# firecam.net
KiCad netlist of a schematic drawn in EAGLE
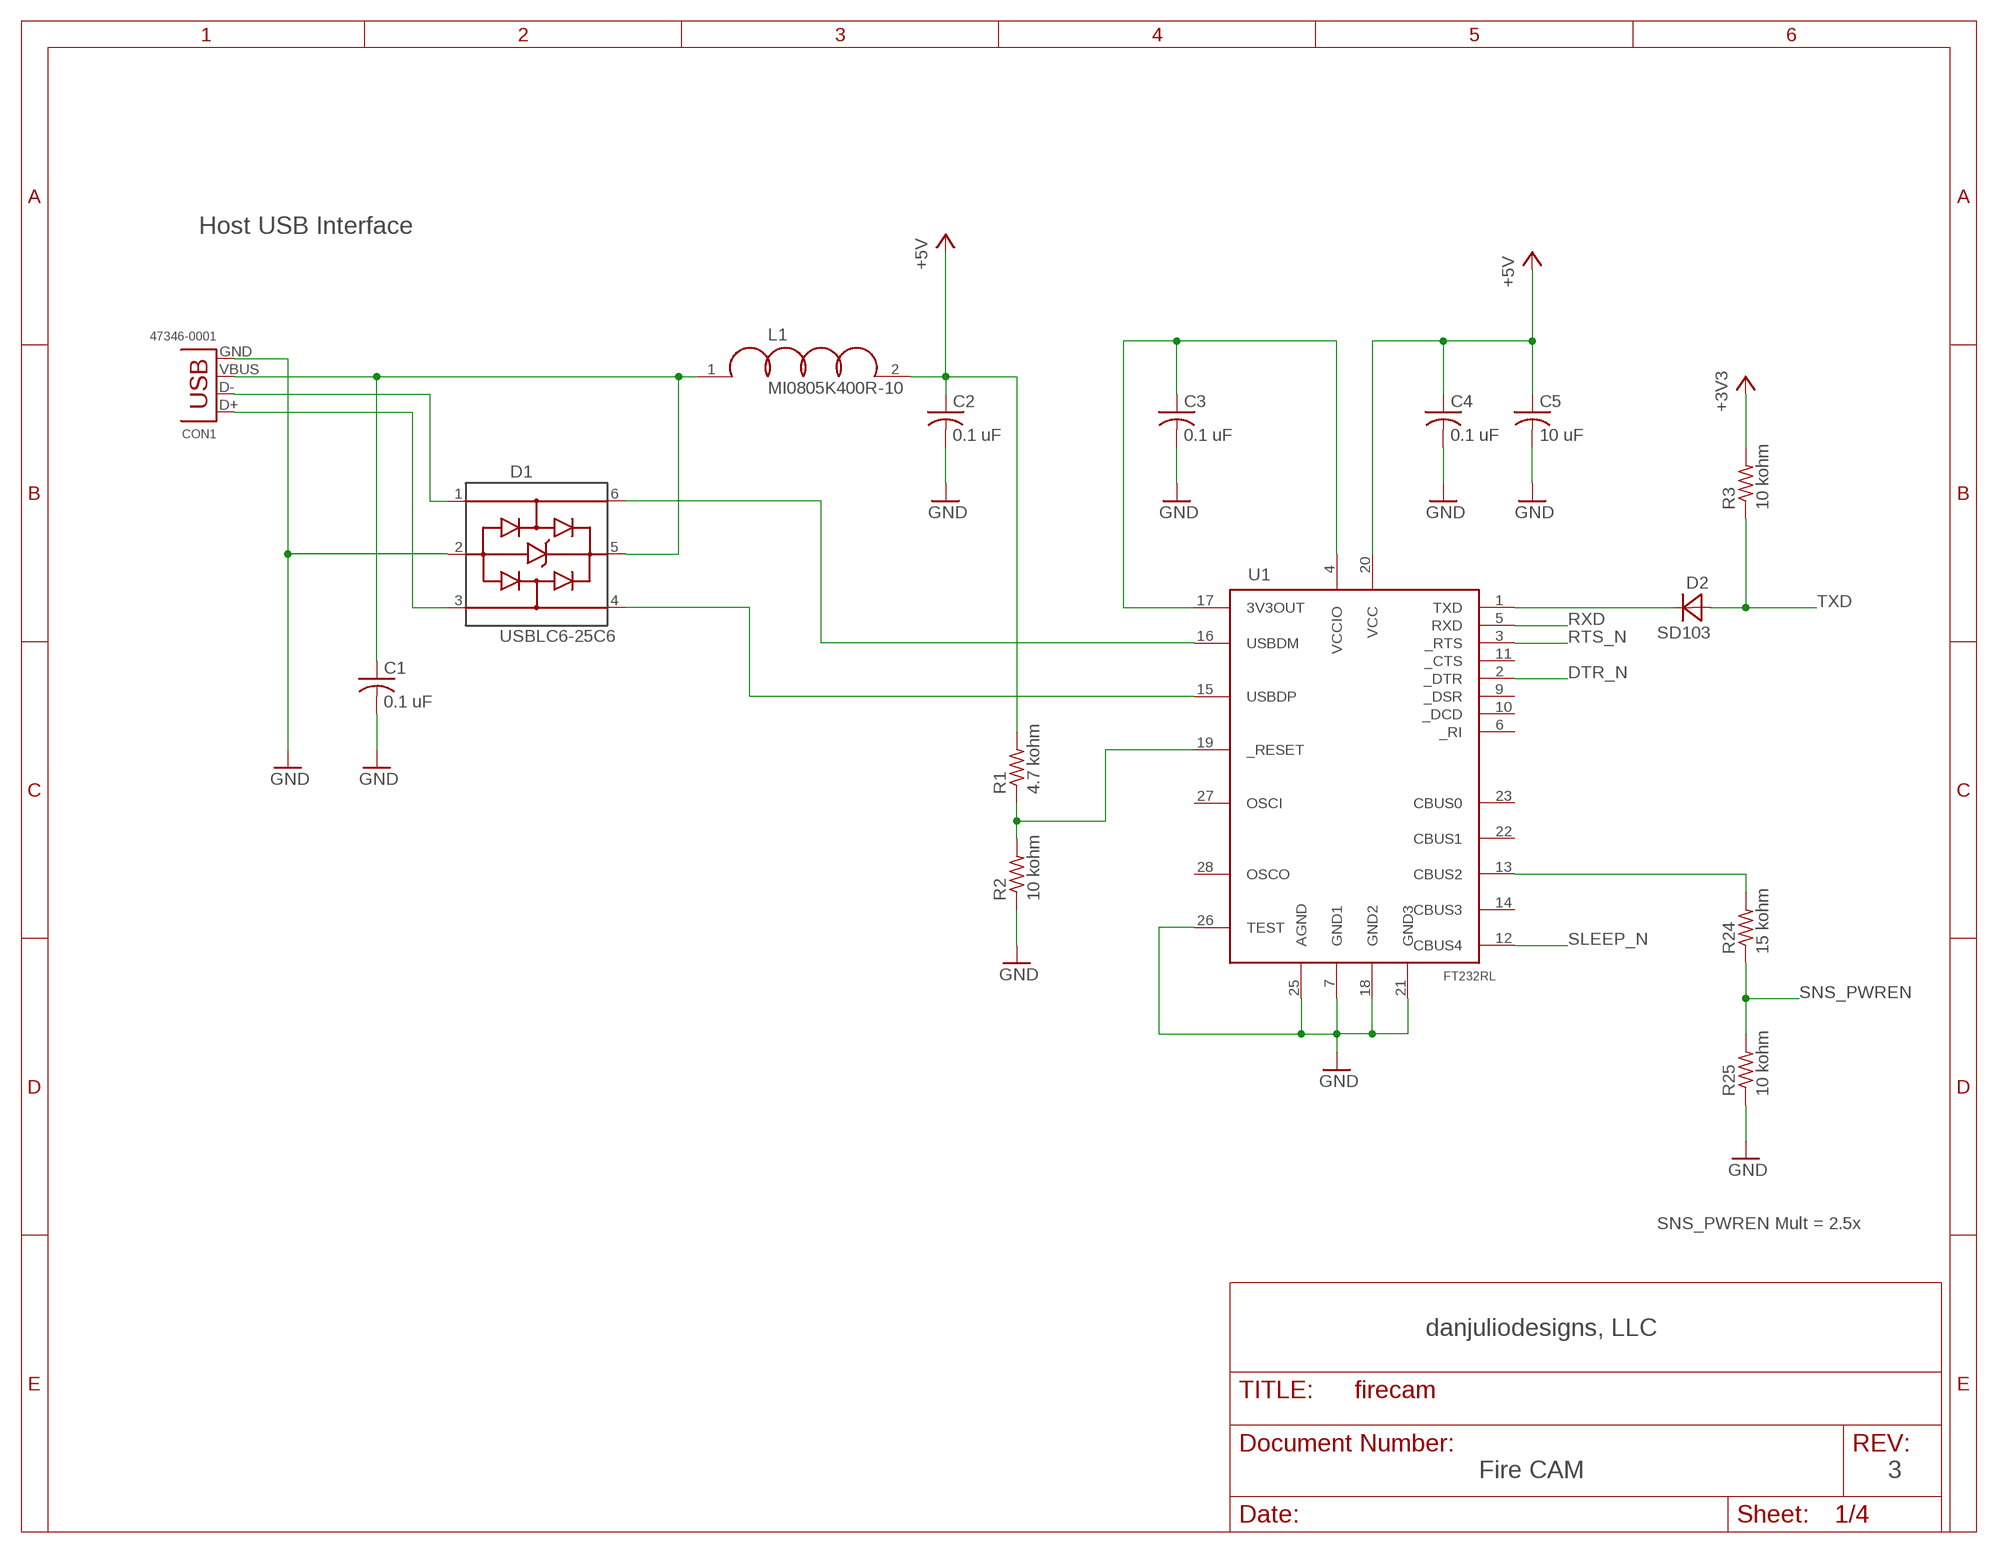
[diagram p0: schematic, sheet 1]
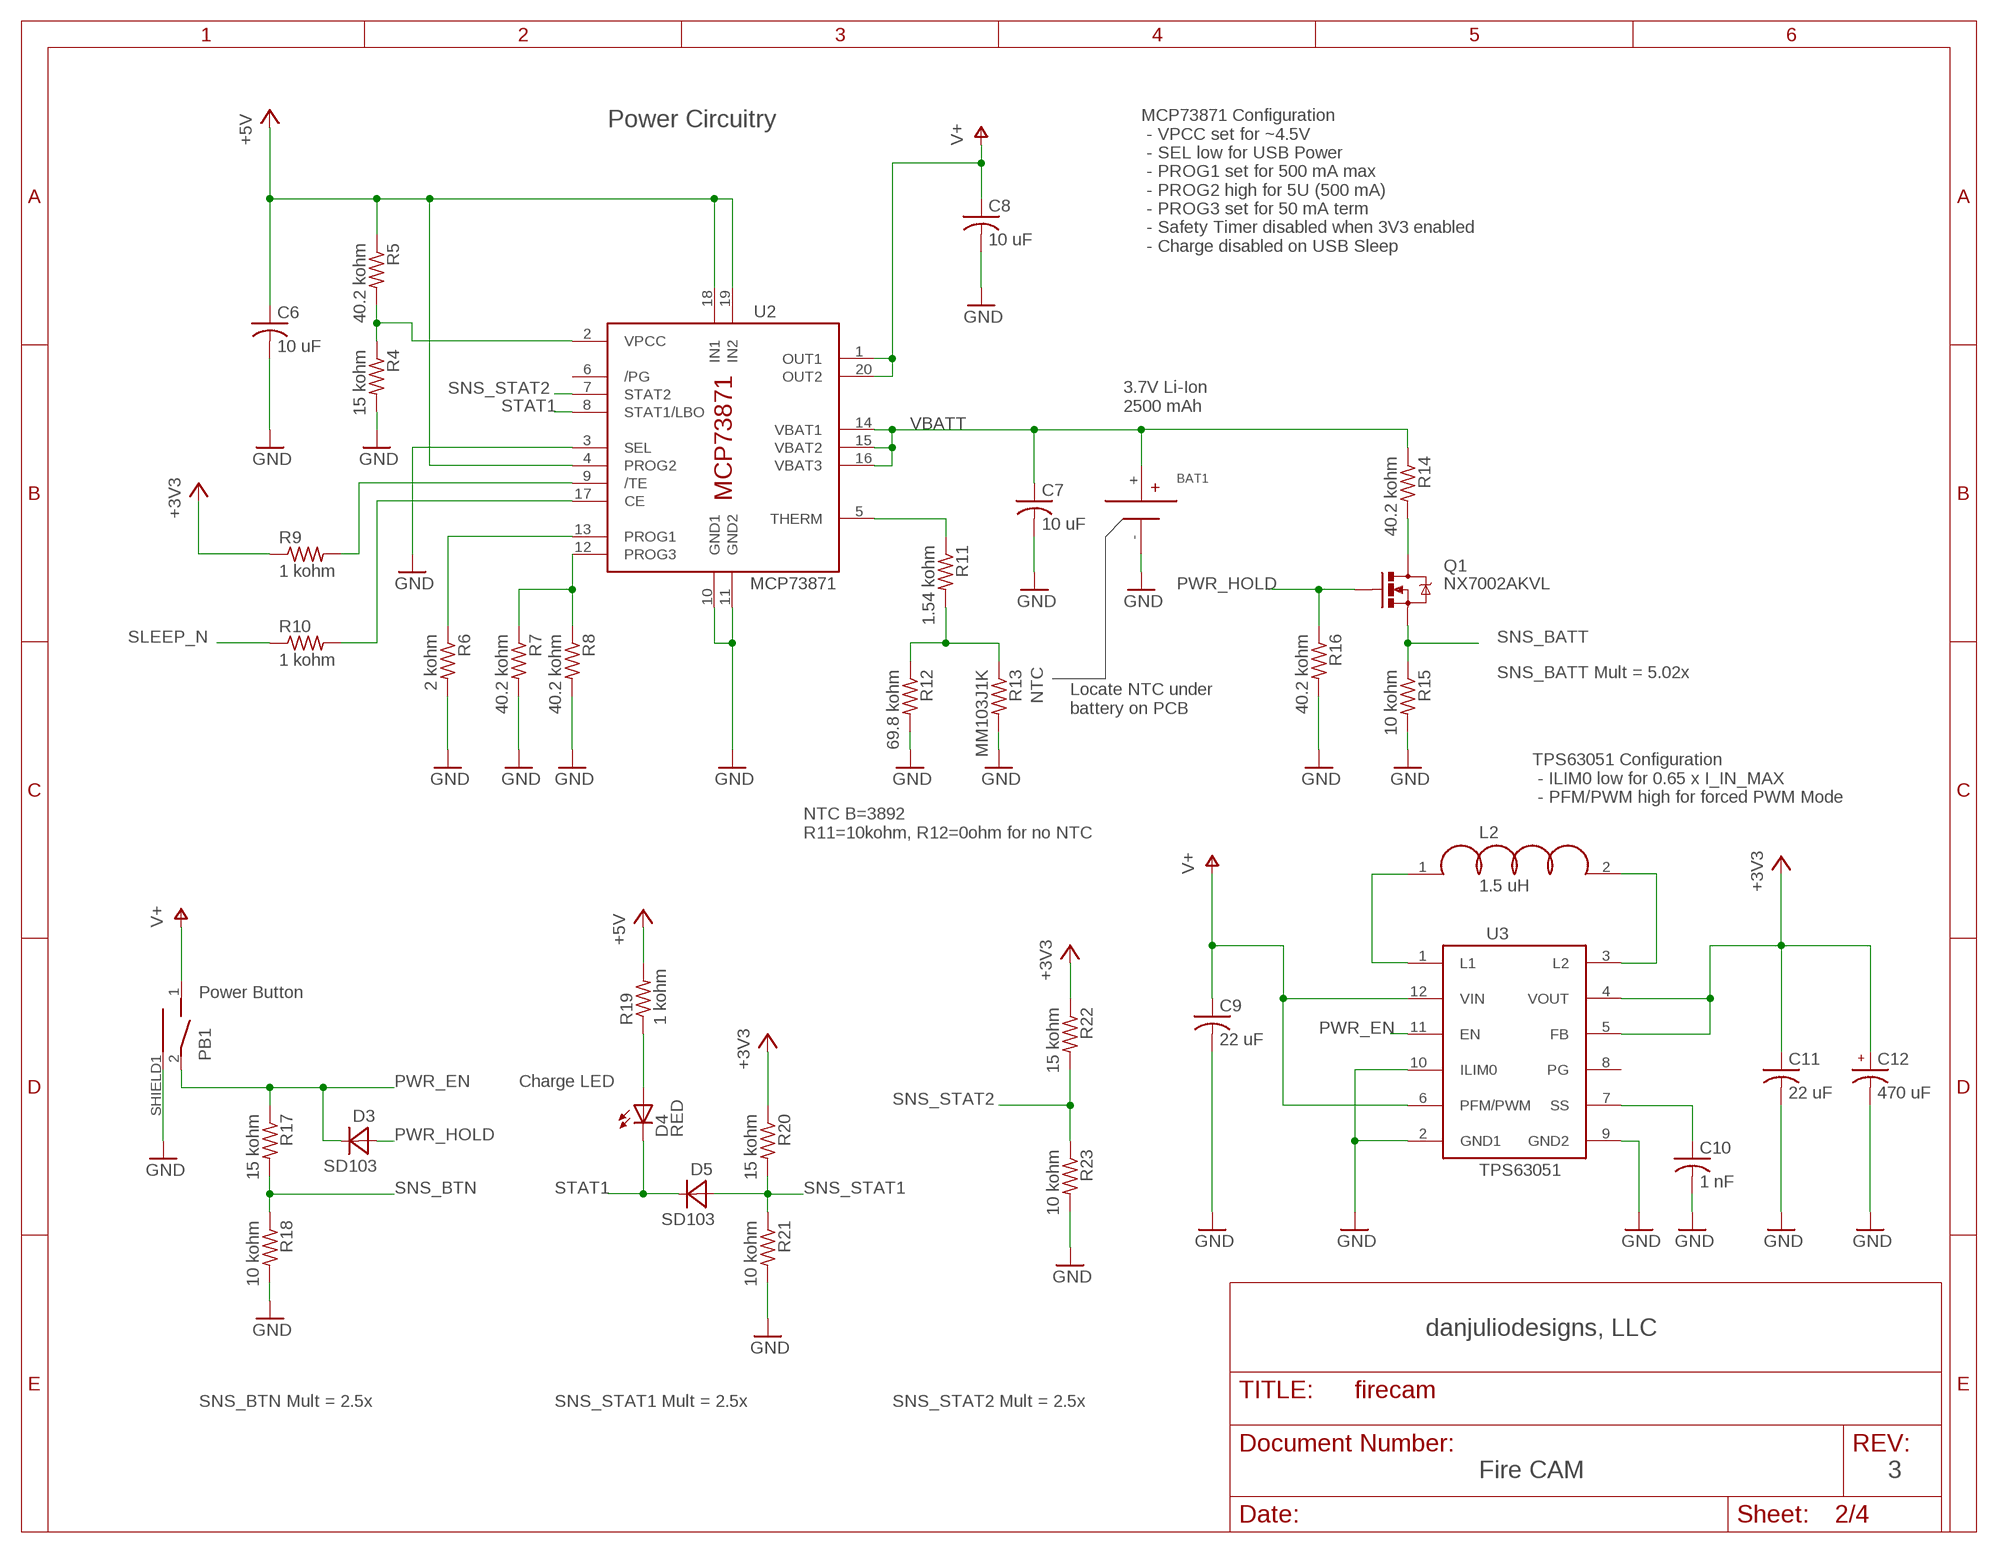
[diagram p1: schematic, sheet 2]
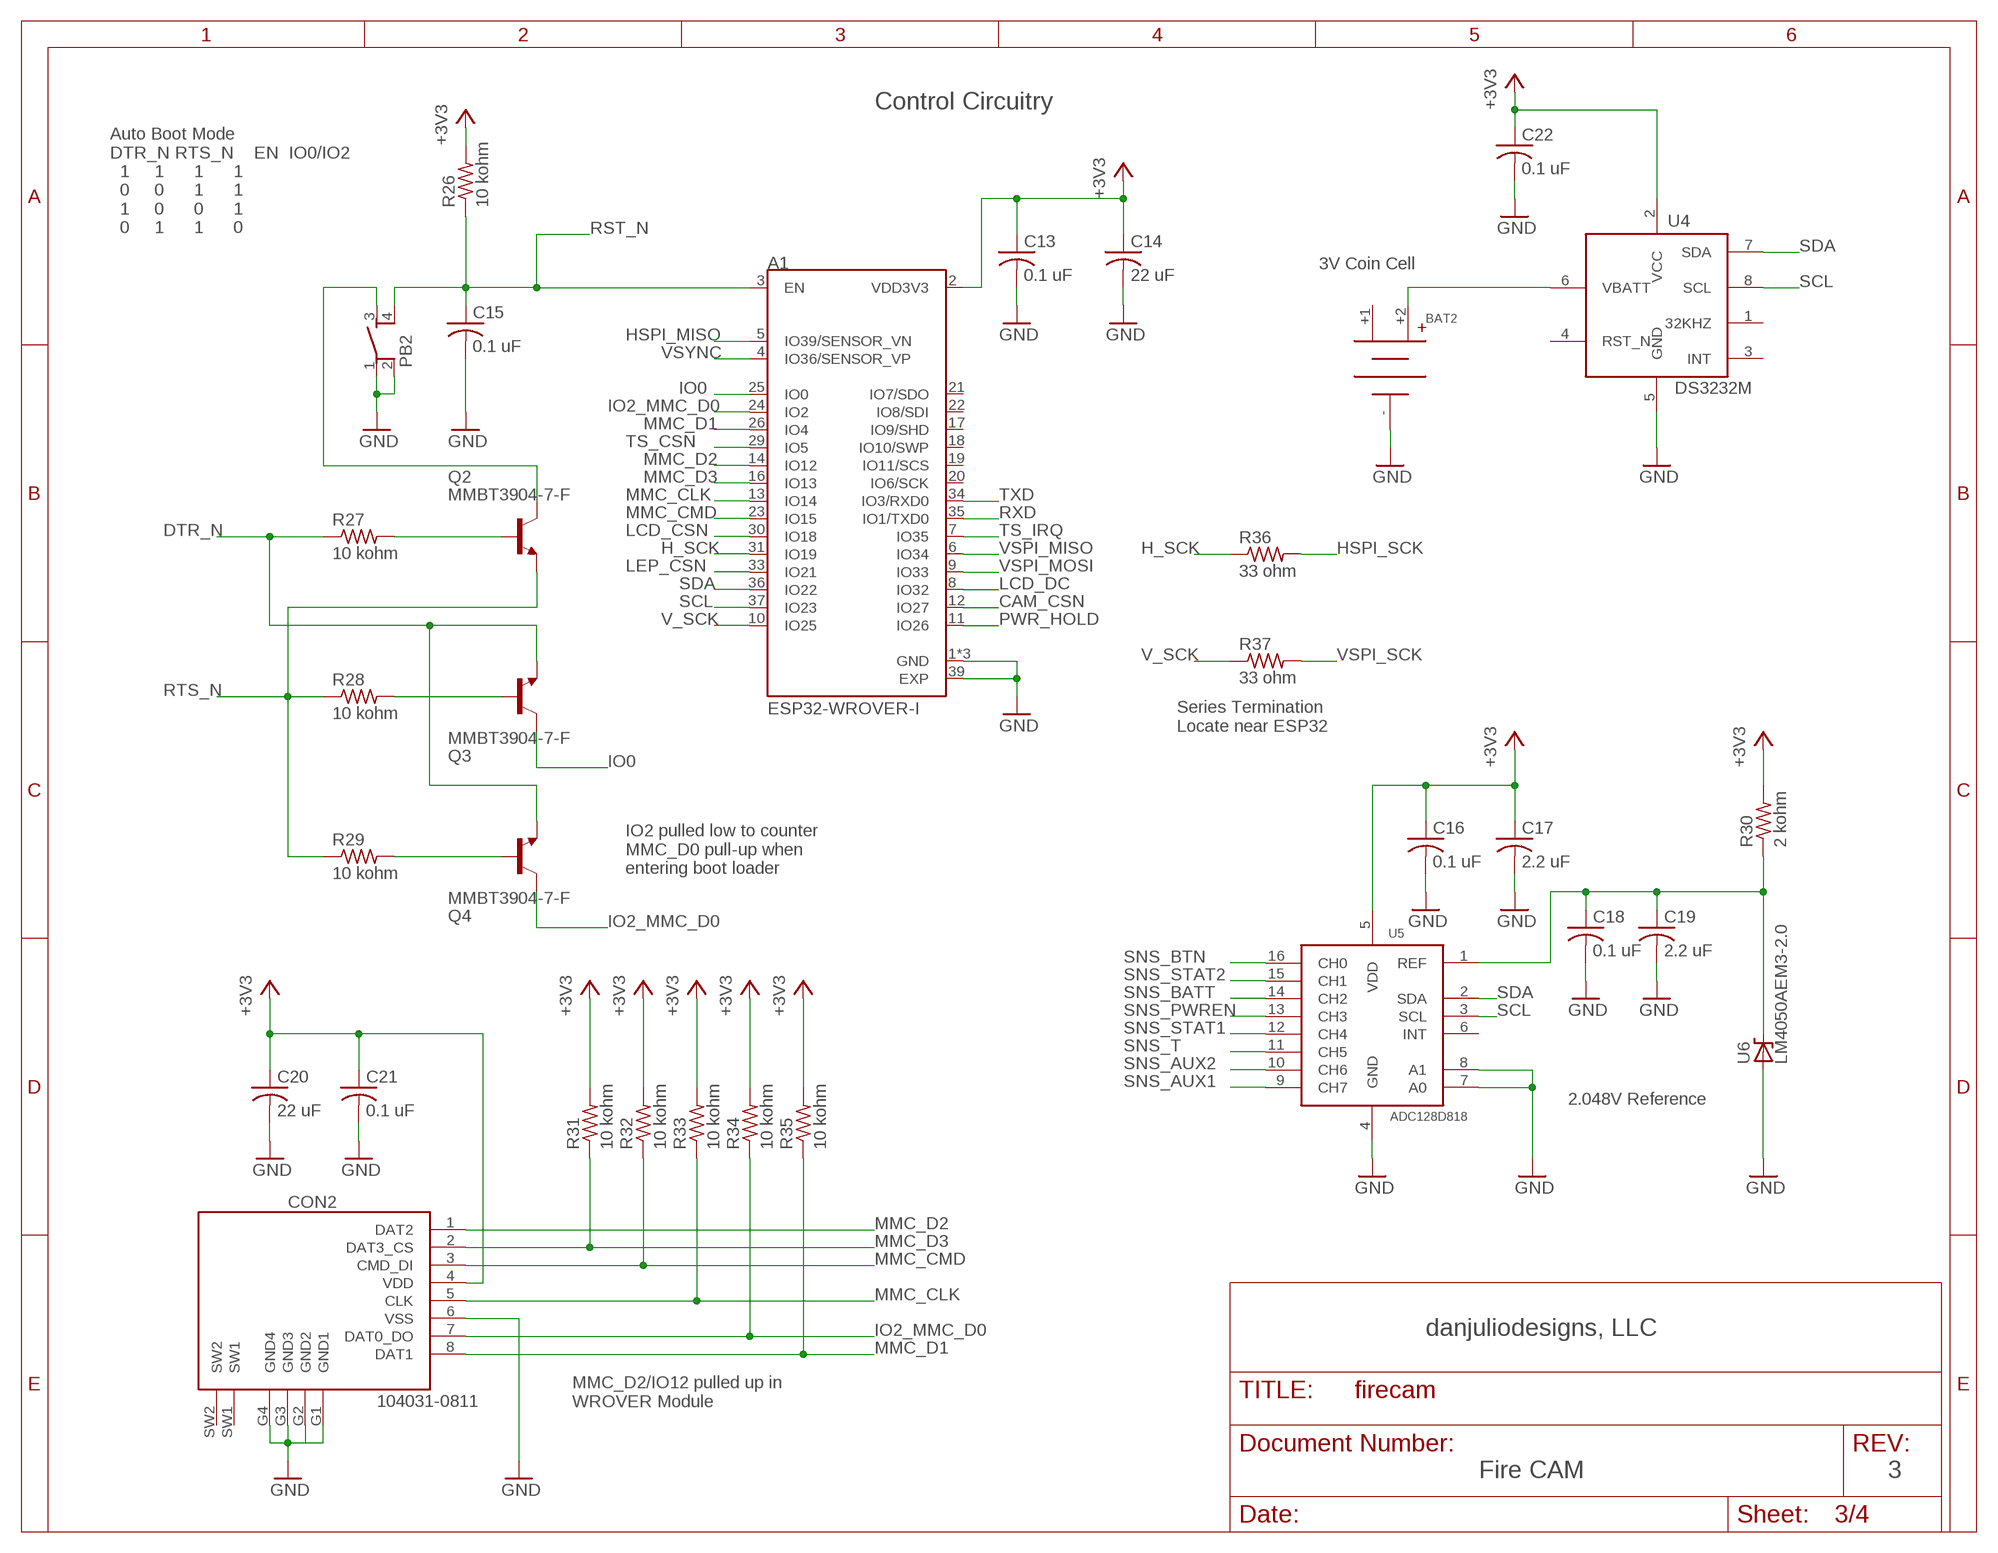
[diagram p2: schematic, sheet 3]
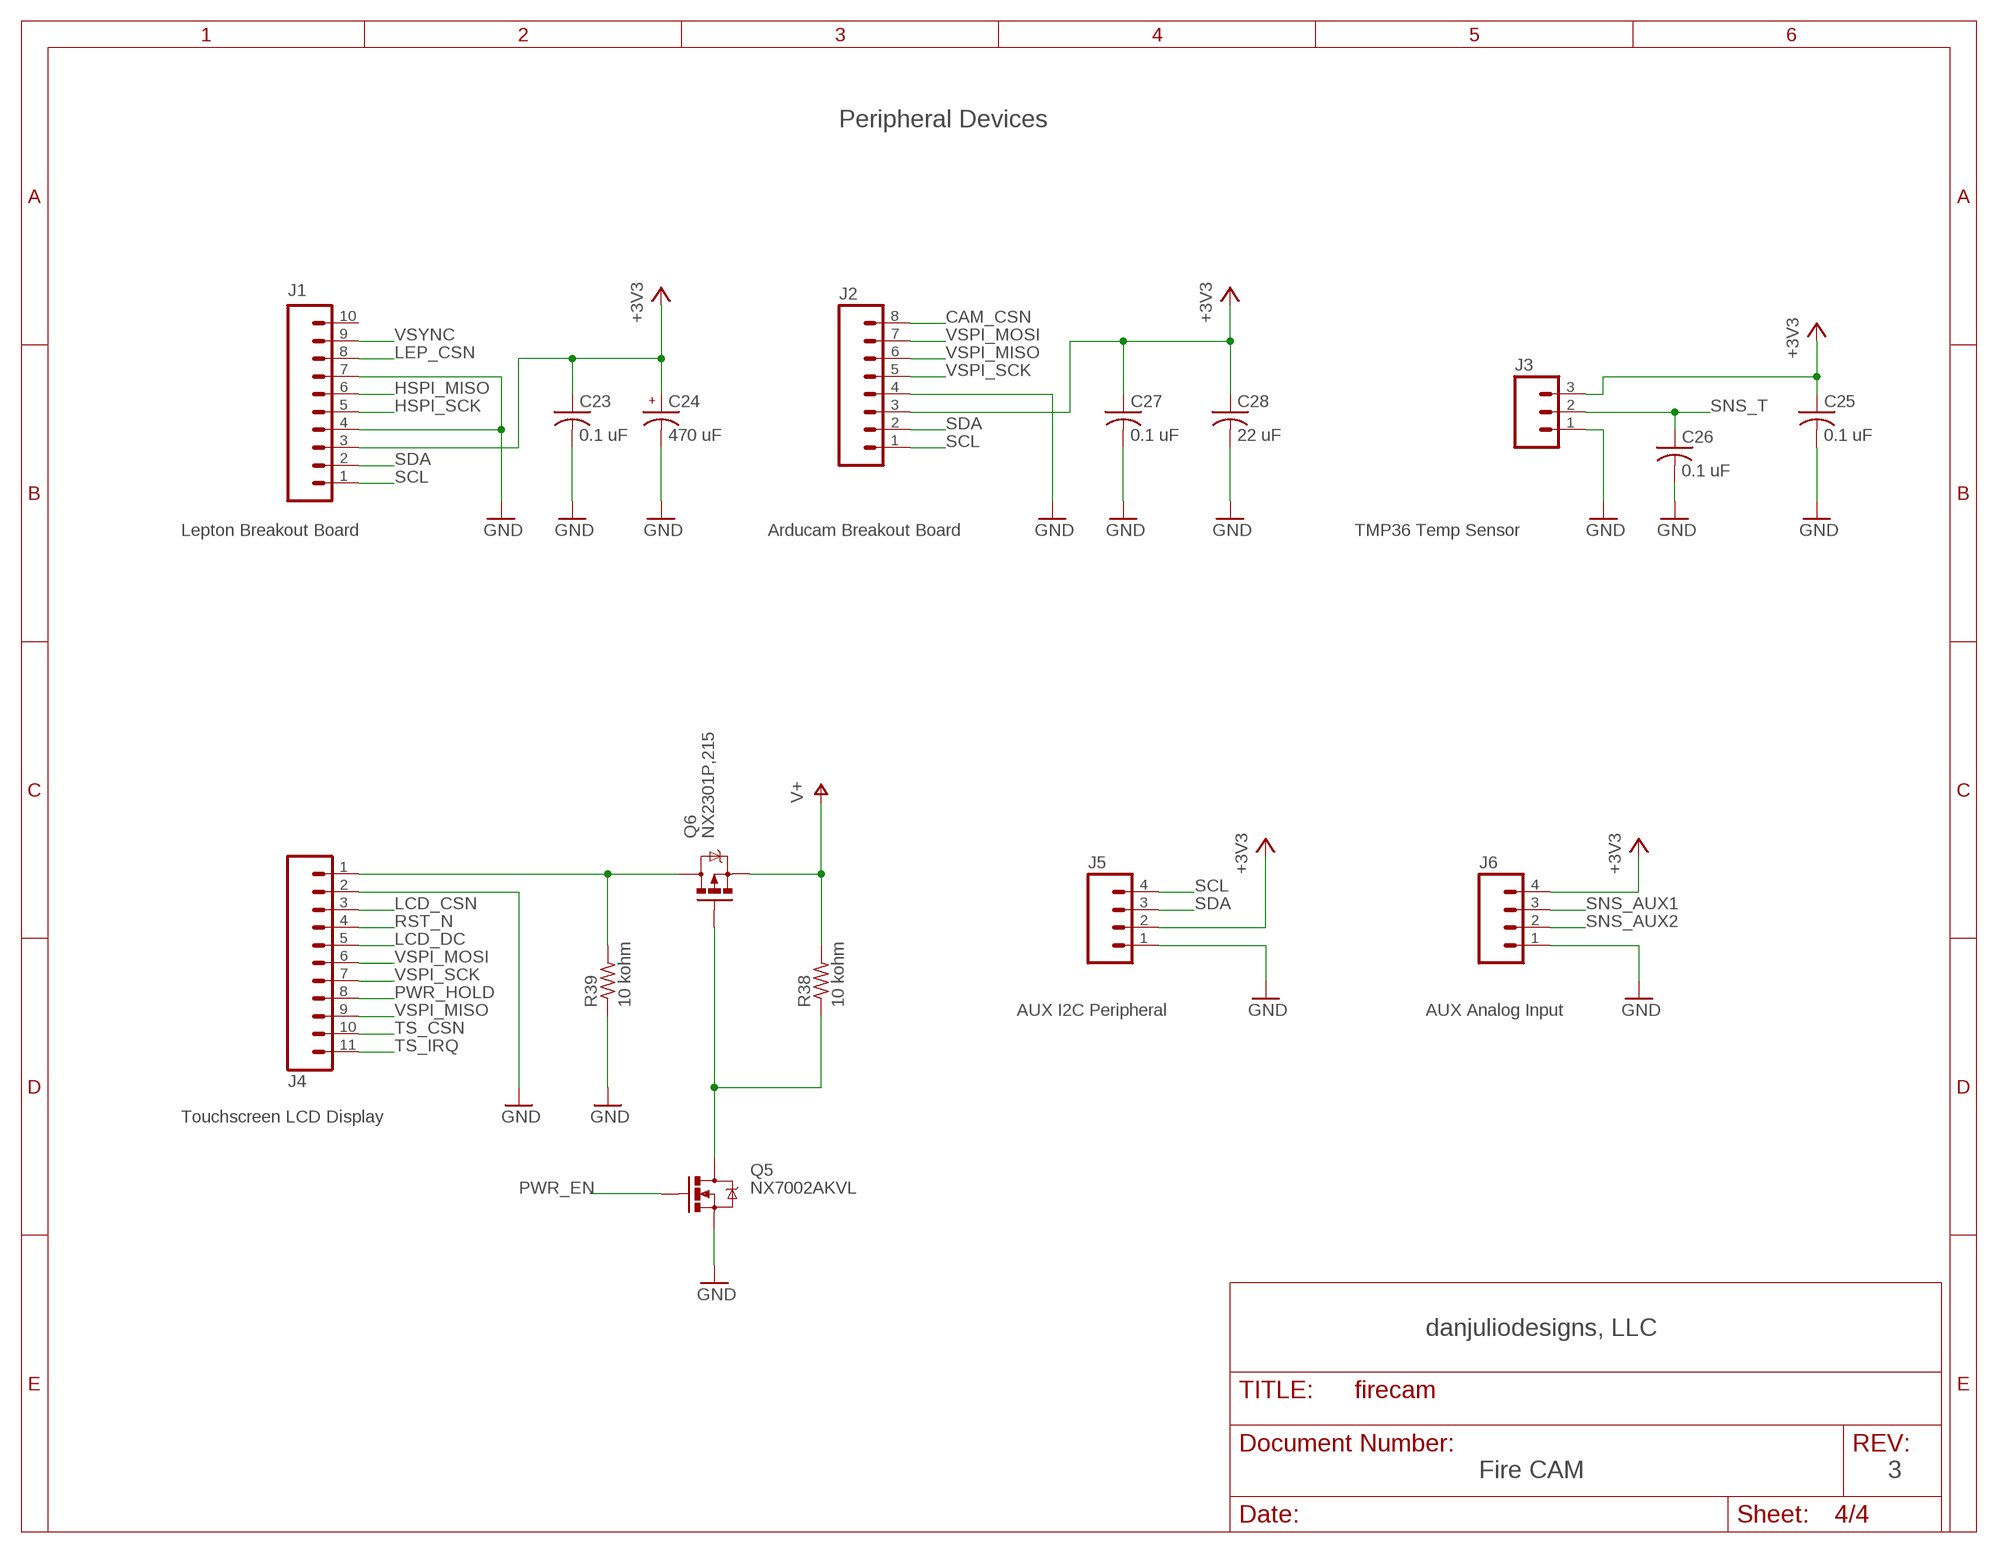
[diagram p3: schematic, sheet 4]

(export (version "E")
  (design (tool "Eeschema 10.0.6"))
  (components
    (comp (ref "C23")
      (value "0.1 uF")
      (footprint "eagle-import:C0603")
      (libsource (lib "eagle-import") (part "C-USSMT0603"))
    )
    (comp (ref "C24")
      (value "470 uF")
      (footprint "eagle-import:ECAP-0606")
      (libsource (lib "eagle-import") (part "CPOL-USSMT06X06"))
    )
    (comp (ref "C25")
      (value "0.1 uF")
      (footprint "eagle-import:C0603")
      (libsource (lib "eagle-import") (part "C-USSMT0603"))
    )
    (comp (ref "C26")
      (value "0.1 uF")
      (footprint "eagle-import:C0603")
      (libsource (lib "eagle-import") (part "C-USSMT0603"))
    )
    (comp (ref "C27")
      (value "0.1 uF")
      (footprint "eagle-import:C0603")
      (libsource (lib "eagle-import") (part "C-USSMT0603"))
    )
    (comp (ref "C28")
      (value "22 uF")
      (footprint "eagle-import:C0603")
      (libsource (lib "eagle-import") (part "C-USSMT0603"))
    )
    (comp (ref "J1")
      (value "M10SILK_FEMALE_PTH")
      (footprint "eagle-import:1X10")
      (libsource (lib "eagle-import") (part "M10SILK_FEMALE_PTH"))
    )
    (comp (ref "J2")
      (value "M08SILK_FEMALE_PTH")
      (footprint "eagle-import:1X08")
      (libsource (lib "eagle-import") (part "M08SILK_FEMALE_PTH"))
    )
    (comp (ref "J3")
      (value "M03PTH")
      (footprint "eagle-import:1X03")
      (libsource (lib "eagle-import") (part "M03PTH"))
    )
    (comp (ref "J4")
      (value "M11PTH")
      (footprint "eagle-import:1X11")
      (libsource (lib "eagle-import") (part "M11PTH"))
    )
    (comp (ref "J5")
      (value "M04PTH")
      (footprint "eagle-import:1X04")
      (libsource (lib "eagle-import") (part "M04PTH"))
    )
    (comp (ref "J6")
      (value "M04PTH")
      (footprint "eagle-import:1X04")
      (libsource (lib "eagle-import") (part "M04PTH"))
    )
    (comp (ref "Q5")
      (value "NX7002AKVL")
      (footprint "eagle-import:SOT23-3")
      (libsource (lib "eagle-import") (part "MOSFET-NCHANNELSOT23"))
    )
    (comp (ref "Q6")
      (value "NX2301P,215")
      (footprint "eagle-import:SOT23-3")
      (libsource (lib "eagle-import") (part "MOSFET-PCHANNEL"))
    )
    (comp (ref "R38")
      (value "10 kohm")
      (footprint "eagle-import:R0603")
      (libsource (lib "eagle-import") (part "R-USSMT0603"))
    )
    (comp (ref "R39")
      (value "10 kohm")
      (footprint "eagle-import:R0603")
      (libsource (lib "eagle-import") (part "R-USSMT0603"))
    )
    (comp (ref "BAT1")
      (value "18650_BATTERYTH")
      (footprint "eagle-import:KEYSTONE_1043")
      (libsource (lib "eagle-import") (part "18650_BATTERYTH"))
    )
    (comp (ref "C6")
      (value "10 uF")
      (footprint "eagle-import:C0603")
      (libsource (lib "eagle-import") (part "C-USSMT0603"))
    )
    (comp (ref "C7")
      (value "10 uF")
      (footprint "eagle-import:C0603")
      (libsource (lib "eagle-import") (part "C-USSMT0603"))
    )
    (comp (ref "C8")
      (value "10 uF")
      (footprint "eagle-import:C0603")
      (libsource (lib "eagle-import") (part "C-USSMT0603"))
    )
    (comp (ref "C9")
      (value "22 uF")
      (footprint "eagle-import:C0603")
      (libsource (lib "eagle-import") (part "C-USSMT0603"))
    )
    (comp (ref "C10")
      (value "1 nF")
      (footprint "eagle-import:C0603")
      (libsource (lib "eagle-import") (part "C-USSMT0603"))
    )
    (comp (ref "C11")
      (value "22 uF")
      (footprint "eagle-import:C0603")
      (libsource (lib "eagle-import") (part "C-USSMT0603"))
    )
    (comp (ref "C12")
      (value "470 uF")
      (footprint "eagle-import:ECAP-0606")
      (libsource (lib "eagle-import") (part "CPOL-USSMT06X06"))
    )
    (comp (ref "D3")
      (value "SD103")
      (footprint "eagle-import:SOD123")
      (libsource (lib "eagle-import") (part "DIODESMT_SOD123"))
    )
    (comp (ref "D4")
      (value "RED")
      (footprint "eagle-import:LUMEX_3MM_SMT")
      (libsource (lib "eagle-import") (part "LEDLUMEX_SMT_3MM"))
    )
    (comp (ref "D5")
      (value "SD103")
      (footprint "eagle-import:SOD123")
      (libsource (lib "eagle-import") (part "DIODESMT_SOD123"))
    )
    (comp (ref "L2")
      (value "1.5 uH")
      (footprint "eagle-import:L1008")
      (libsource (lib "eagle-import") (part "INDUCTORSMT1008"))
    )
    (comp (ref "PB1")
      (value "PB_SMT_SIDEPTS645")
      (footprint "eagle-import:PTS645_SIDE_TH")
      (libsource (lib "eagle-import") (part "PB_SMT_SIDEPTS645"))
    )
    (comp (ref "Q1")
      (value "NX7002AKVL")
      (footprint "eagle-import:SOT23-3")
      (libsource (lib "eagle-import") (part "MOSFET-NCHANNELSOT23"))
    )
    (comp (ref "R4")
      (value "15 kohm")
      (footprint "eagle-import:R0603")
      (libsource (lib "eagle-import") (part "R-USSMT0603"))
    )
    (comp (ref "R5")
      (value "40.2 kohm")
      (footprint "eagle-import:R0603")
      (libsource (lib "eagle-import") (part "R-USSMT0603"))
    )
    (comp (ref "R6")
      (value "2 kohm")
      (footprint "eagle-import:R0603")
      (libsource (lib "eagle-import") (part "R-USSMT0603"))
    )
    (comp (ref "R7")
      (value "40.2 kohm")
      (footprint "eagle-import:R0603")
      (libsource (lib "eagle-import") (part "R-USSMT0603"))
    )
    (comp (ref "R8")
      (value "40.2 kohm")
      (footprint "eagle-import:R0603")
      (libsource (lib "eagle-import") (part "R-USSMT0603"))
    )
    (comp (ref "R9")
      (value "1 kohm")
      (footprint "eagle-import:R0603")
      (libsource (lib "eagle-import") (part "R-USSMT0603"))
    )
    (comp (ref "R10")
      (value "1 kohm")
      (footprint "eagle-import:R0603")
      (libsource (lib "eagle-import") (part "R-USSMT0603"))
    )
    (comp (ref "R11")
      (value "1.54 kohm")
      (footprint "eagle-import:R0603")
      (libsource (lib "eagle-import") (part "R-USSMT0603"))
    )
    (comp (ref "R12")
      (value "69.8 kohm")
      (footprint "eagle-import:R0603")
      (libsource (lib "eagle-import") (part "R-USSMT0603"))
    )
    (comp (ref "R13")
      (value "MM103J1K")
      (footprint "eagle-import:R0603")
      (libsource (lib "eagle-import") (part "R-USSMT0603"))
    )
    (comp (ref "R14")
      (value "40.2 kohm")
      (footprint "eagle-import:R0603")
      (libsource (lib "eagle-import") (part "R-USSMT0603"))
    )
    (comp (ref "R15")
      (value "10 kohm")
      (footprint "eagle-import:R0603")
      (libsource (lib "eagle-import") (part "R-USSMT0603"))
    )
    (comp (ref "R16")
      (value "40.2 kohm")
      (footprint "eagle-import:R0603")
      (libsource (lib "eagle-import") (part "R-USSMT0603"))
    )
    (comp (ref "R17")
      (value "15 kohm")
      (footprint "eagle-import:R0603")
      (libsource (lib "eagle-import") (part "R-USSMT0603"))
    )
    (comp (ref "R18")
      (value "10 kohm")
      (footprint "eagle-import:R0603")
      (libsource (lib "eagle-import") (part "R-USSMT0603"))
    )
    (comp (ref "R19")
      (value "1 kohm")
      (footprint "eagle-import:R0603")
      (libsource (lib "eagle-import") (part "R-USSMT0603"))
    )
    (comp (ref "R20")
      (value "15 kohm")
      (footprint "eagle-import:R0603")
      (libsource (lib "eagle-import") (part "R-USSMT0603"))
    )
    (comp (ref "R21")
      (value "10 kohm")
      (footprint "eagle-import:R0603")
      (libsource (lib "eagle-import") (part "R-USSMT0603"))
    )
    (comp (ref "R22")
      (value "15 kohm")
      (footprint "eagle-import:R0603")
      (libsource (lib "eagle-import") (part "R-USSMT0603"))
    )
    (comp (ref "R23")
      (value "10 kohm")
      (footprint "eagle-import:R0603")
      (libsource (lib "eagle-import") (part "R-USSMT0603"))
    )
    (comp (ref "U2")
      (value "MCP73871")
      (footprint "eagle-import:QFN20")
      (libsource (lib "eagle-import") (part "MCP73871"))
    )
    (comp (ref "U3")
      (value "TPS63051")
      (footprint "eagle-import:HOTROD_QFN12")
      (libsource (lib "eagle-import") (part "TPS63051_QFN"))
    )
    (comp (ref "A1")
      (value "ESP32-WROVER-I")
      (footprint "eagle-import:XCVR_ESP32-WROVER-I")
      (fields (field (name "MF") "Espressif Systems"))
      (libsource (lib "eagle-import") (part "ESP32-WROVER-I"))
    )
    (comp (ref "BAT2")
      (value "COIN_CELL12MM")
      (footprint "eagle-import:KEYSTONE_3001")
      (libsource (lib "eagle-import") (part "COIN_CELL12MM"))
    )
    (comp (ref "C13")
      (value "0.1 uF")
      (footprint "eagle-import:C0603")
      (libsource (lib "eagle-import") (part "C-USSMT0603"))
    )
    (comp (ref "C14")
      (value "22 uF")
      (footprint "eagle-import:C0603")
      (libsource (lib "eagle-import") (part "C-USSMT0603"))
    )
    (comp (ref "C15")
      (value "0.1 uF")
      (footprint "eagle-import:C0603")
      (libsource (lib "eagle-import") (part "C-USSMT0603"))
    )
    (comp (ref "C16")
      (value "0.1 uF")
      (footprint "eagle-import:C0603")
      (libsource (lib "eagle-import") (part "C-USSMT0603"))
    )
    (comp (ref "C17")
      (value "2.2 uF")
      (footprint "eagle-import:C0603")
      (libsource (lib "eagle-import") (part "C-USSMT0603"))
    )
    (comp (ref "C18")
      (value "0.1 uF")
      (footprint "eagle-import:C0603")
      (libsource (lib "eagle-import") (part "C-USSMT0603"))
    )
    (comp (ref "C19")
      (value "2.2 uF")
      (footprint "eagle-import:C0603")
      (libsource (lib "eagle-import") (part "C-USSMT0603"))
    )
    (comp (ref "C20")
      (value "22 uF")
      (footprint "eagle-import:C0603")
      (libsource (lib "eagle-import") (part "C-USSMT0603"))
    )
    (comp (ref "C21")
      (value "0.1 uF")
      (footprint "eagle-import:C0603")
      (libsource (lib "eagle-import") (part "C-USSMT0603"))
    )
    (comp (ref "C22")
      (value "0.1 uF")
      (footprint "eagle-import:C0603")
      (libsource (lib "eagle-import") (part "C-USSMT0603"))
    )
    (comp (ref "CON2")
      (value "104031-0811")
      (footprint "eagle-import:MOLEX_1040310811")
      (libsource (lib "eagle-import") (part "MOLEX_1040310811"))
    )
    (comp (ref "PB2")
      (value "PB_TACT_4SMTR92")
      (footprint "eagle-import:CK_PTS645_SMT")
      (libsource (lib "eagle-import") (part "PB_TACT_4SMTR92"))
    )
    (comp (ref "Q2")
      (value "MMBT3904-7-F")
      (footprint "eagle-import:SOT23-BEC")
      (libsource (lib "eagle-import") (part "-NPN-SOT23-BECBC808"))
    )
    (comp (ref "Q3")
      (value "MMBT3904-7-F")
      (footprint "eagle-import:SOT23-BEC")
      (libsource (lib "eagle-import") (part "-NPN-SOT23-BECBC808"))
    )
    (comp (ref "Q4")
      (value "MMBT3904-7-F")
      (footprint "eagle-import:SOT23-BEC")
      (libsource (lib "eagle-import") (part "-NPN-SOT23-BECBC808"))
    )
    (comp (ref "R26")
      (value "10 kohm")
      (footprint "eagle-import:R0603")
      (libsource (lib "eagle-import") (part "R-USSMT0603"))
    )
    (comp (ref "R27")
      (value "10 kohm")
      (footprint "eagle-import:R0603")
      (libsource (lib "eagle-import") (part "R-USSMT0603"))
    )
    (comp (ref "R28")
      (value "10 kohm")
      (footprint "eagle-import:R0603")
      (libsource (lib "eagle-import") (part "R-USSMT0603"))
    )
    (comp (ref "R29")
      (value "10 kohm")
      (footprint "eagle-import:R0603")
      (libsource (lib "eagle-import") (part "R-USSMT0603"))
    )
    (comp (ref "R30")
      (value "2 kohm")
      (footprint "eagle-import:R0603")
      (libsource (lib "eagle-import") (part "R-USSMT0603"))
    )
    (comp (ref "R31")
      (value "10 kohm")
      (footprint "eagle-import:R0603")
      (libsource (lib "eagle-import") (part "R-USSMT0603"))
    )
    (comp (ref "R32")
      (value "10 kohm")
      (footprint "eagle-import:R0603")
      (libsource (lib "eagle-import") (part "R-USSMT0603"))
    )
    (comp (ref "R33")
      (value "10 kohm")
      (footprint "eagle-import:R0603")
      (libsource (lib "eagle-import") (part "R-USSMT0603"))
    )
    (comp (ref "R34")
      (value "10 kohm")
      (footprint "eagle-import:R0603")
      (libsource (lib "eagle-import") (part "R-USSMT0603"))
    )
    (comp (ref "R35")
      (value "10 kohm")
      (footprint "eagle-import:R0603")
      (libsource (lib "eagle-import") (part "R-USSMT0603"))
    )
    (comp (ref "R36")
      (value "33 ohm")
      (footprint "eagle-import:R0603")
      (libsource (lib "eagle-import") (part "R-USSMT0603"))
    )
    (comp (ref "R37")
      (value "33 ohm")
      (footprint "eagle-import:R0603")
      (libsource (lib "eagle-import") (part "R-USSMT0603"))
    )
    (comp (ref "U4")
      (value "DS3232M")
      (footprint "eagle-import:SO8")
      (libsource (lib "eagle-import") (part "DS3232M"))
    )
    (comp (ref "U5")
      (value "ADC128D818")
      (footprint "eagle-import:SSOP16")
      (libsource (lib "eagle-import") (part "ADC128D818"))
    )
    (comp (ref "U6")
      (value "LM4050AEM3-2.0")
      (footprint "eagle-import:SOT23-3")
      (libsource (lib "eagle-import") (part "VOLTAGE_REFSMT_SOT23"))
    )
    (comp (ref "C1")
      (value "0.1 uF")
      (footprint "eagle-import:C0603")
      (libsource (lib "eagle-import") (part "C-USSMT0603"))
    )
    (comp (ref "C2")
      (value "0.1 uF")
      (footprint "eagle-import:C0603")
      (libsource (lib "eagle-import") (part "C-USSMT0603"))
    )
    (comp (ref "C3")
      (value "0.1 uF")
      (footprint "eagle-import:C0603")
      (libsource (lib "eagle-import") (part "C-USSMT0603"))
    )
    (comp (ref "C4")
      (value "0.1 uF")
      (footprint "eagle-import:C0603")
      (libsource (lib "eagle-import") (part "C-USSMT0603"))
    )
    (comp (ref "C5")
      (value "10 uF")
      (footprint "eagle-import:C0603")
      (libsource (lib "eagle-import") (part "C-USSMT0603"))
    )
    (comp (ref "CON1")
      (value "47346-0001")
      (footprint "eagle-import:USB_MICROB_SMT")
      (libsource (lib "eagle-import") (part "USBMICROB"))
    )
    (comp (ref "D1")
      (value "USBLC6-25C6")
      (footprint "eagle-import:SOT23-6")
      (libsource (lib "eagle-import") (part "USBLC6-2SOT23-6"))
    )
    (comp (ref "D2")
      (value "SD103")
      (footprint "eagle-import:SOD123")
      (libsource (lib "eagle-import") (part "DIODESMT_SOD123"))
    )
    (comp (ref "L1")
      (value "MI0805K400R-10")
      (footprint "eagle-import:L0805")
      (libsource (lib "eagle-import") (part "INDUCTORSMT0805"))
    )
    (comp (ref "R1")
      (value "4.7 kohm")
      (footprint "eagle-import:R0603")
      (libsource (lib "eagle-import") (part "R-USSMT0603"))
    )
    (comp (ref "R2")
      (value "10 kohm")
      (footprint "eagle-import:R0603")
      (libsource (lib "eagle-import") (part "R-USSMT0603"))
    )
    (comp (ref "R3")
      (value "10 kohm")
      (footprint "eagle-import:R0603")
      (libsource (lib "eagle-import") (part "R-USSMT0603"))
    )
    (comp (ref "R24")
      (value "15 kohm")
      (footprint "eagle-import:R0603")
      (libsource (lib "eagle-import") (part "R-USSMT0603"))
    )
    (comp (ref "R25")
      (value "10 kohm")
      (footprint "eagle-import:R0603")
      (libsource (lib "eagle-import") (part "R-USSMT0603"))
    )
    (comp (ref "U1")
      (value "FT232RL")
      (footprint "eagle-import:SSOP28DB")
      (libsource (lib "eagle-import") (part "FT232RLSSOP28"))
    )
  )
  (nets
    (net (code "1") (name "+1") (class "Default")
      (node (ref "BAT2") (pin "+1") (pinfunction "+1_+1") (pintype "power_in"))
    )
    (net (code "2") (name "+3V3") (class "Default")
      (node (ref "A1") (pin "2") (pinfunction "VDD3V3_2") (pintype "power_in"))
      (node (ref "C11") (pin "1") (pinfunction "1_1") (pintype "passive"))
      (node (ref "C12") (pin "+") (pinfunction "1_+") (pintype "passive"))
      (node (ref "C13") (pin "1") (pinfunction "1_1") (pintype "passive"))
      (node (ref "C14") (pin "1") (pinfunction "1_1") (pintype "passive"))
      (node (ref "C16") (pin "1") (pinfunction "1_1") (pintype "passive"))
      (node (ref "C17") (pin "1") (pinfunction "1_1") (pintype "passive"))
      (node (ref "C20") (pin "1") (pinfunction "1_1") (pintype "passive"))
      (node (ref "C21") (pin "1") (pinfunction "1_1") (pintype "passive"))
      (node (ref "C22") (pin "1") (pinfunction "1_1") (pintype "passive"))
      (node (ref "C23") (pin "1") (pinfunction "1_1") (pintype "passive"))
      (node (ref "C24") (pin "+") (pinfunction "1_+") (pintype "passive"))
      (node (ref "C25") (pin "1") (pinfunction "1_1") (pintype "passive"))
      (node (ref "C27") (pin "1") (pinfunction "1_1") (pintype "passive"))
      (node (ref "C28") (pin "1") (pinfunction "1_1") (pintype "passive"))
      (node (ref "CON2") (pin "4") (pinfunction "VDD_4") (pintype "power_in"))
      (node (ref "J1") (pin "3") (pinfunction "3_3") (pintype "passive"))
      (node (ref "J2") (pin "3") (pinfunction "3_3") (pintype "passive"))
      (node (ref "J3") (pin "3") (pinfunction "3_3") (pintype "passive"))
      (node (ref "J5") (pin "2") (pinfunction "2_2") (pintype "passive"))
      (node (ref "J6") (pin "4") (pinfunction "4_4") (pintype "passive"))
      (node (ref "R20") (pin "1") (pinfunction "1_1") (pintype "passive"))
      (node (ref "R22") (pin "1") (pinfunction "1_1") (pintype "passive"))
      (node (ref "R26") (pin "2") (pinfunction "2_2") (pintype "passive"))
      (node (ref "R3") (pin "2") (pinfunction "2_2") (pintype "passive"))
      (node (ref "R30") (pin "2") (pinfunction "2_2") (pintype "passive"))
      (node (ref "R31") (pin "2") (pinfunction "2_2") (pintype "passive"))
      (node (ref "R32") (pin "2") (pinfunction "2_2") (pintype "passive"))
      (node (ref "R33") (pin "2") (pinfunction "2_2") (pintype "passive"))
      (node (ref "R34") (pin "2") (pinfunction "2_2") (pintype "passive"))
      (node (ref "R35") (pin "2") (pinfunction "2_2") (pintype "passive"))
      (node (ref "R9") (pin "1") (pinfunction "1_1") (pintype "passive"))
      (node (ref "U3") (pin "4") (pinfunction "VOUT_4") (pintype "bidirectional"))
      (node (ref "U3") (pin "5") (pinfunction "FB_5") (pintype "passive"))
      (node (ref "U4") (pin "2") (pinfunction "VCC_2") (pintype "power_in"))
      (node (ref "U5") (pin "5") (pinfunction "VDD_5") (pintype "power_in"))
    )
    (net (code "3") (name "+5V") (class "Default")
      (node (ref "C2") (pin "1") (pinfunction "1_1") (pintype "passive"))
      (node (ref "C4") (pin "1") (pinfunction "1_1") (pintype "passive"))
      (node (ref "C5") (pin "1") (pinfunction "1_1") (pintype "passive"))
      (node (ref "C6") (pin "1") (pinfunction "1_1") (pintype "passive"))
      (node (ref "L1") (pin "2") (pinfunction "P$2_2") (pintype "passive"))
      (node (ref "R1") (pin "2") (pinfunction "2_2") (pintype "passive"))
      (node (ref "R19") (pin "2") (pinfunction "2_2") (pintype "passive"))
      (node (ref "R5") (pin "1") (pinfunction "1_1") (pintype "passive"))
      (node (ref "U1") (pin "20") (pinfunction "VCC_20") (pintype "power_in"))
      (node (ref "U2") (pin "18") (pinfunction "IN1_18") (pintype "input"))
      (node (ref "U2") (pin "19") (pinfunction "IN2_19") (pintype "input"))
      (node (ref "U2") (pin "4") (pinfunction "PROG2_4") (pintype "input"))
    )
    (net (code "4") (name "CAM_CSN") (class "Default")
      (node (ref "A1") (pin "12") (pinfunction "IO27_12") (pintype "bidirectional"))
      (node (ref "J2") (pin "8") (pinfunction "8_8") (pintype "passive"))
    )
    (net (code "5") (name "DTR_N") (class "Default")
      (node (ref "Q3") (pin "E") (pinfunction "E_E") (pintype "passive"))
      (node (ref "Q4") (pin "E") (pinfunction "E_E") (pintype "passive"))
      (node (ref "R27") (pin "1") (pinfunction "1_1") (pintype "passive"))
      (node (ref "U1") (pin "2") (pinfunction "_DTR_2") (pintype "output"))
    )
    (net (code "6") (name "GND") (class "Default")
      (node (ref "A1") (pin "1") (pinfunction "GND_1") (pintype "power_in"))
      (node (ref "A1") (pin "15") (pinfunction "GND_15") (pintype "power_in"))
      (node (ref "A1") (pin "38") (pinfunction "GND_38") (pintype "power_in"))
      (node (ref "A1") (pin "39") (pinfunction "EXP_39") (pintype "power_in"))
      (node (ref "BAT1") (pin "-") (pinfunction "-_-") (pintype "power_in"))
      (node (ref "BAT2") (pin "-") (pinfunction "-_-") (pintype "power_in"))
      (node (ref "C1") (pin "2") (pinfunction "2_2") (pintype "passive"))
      (node (ref "C10") (pin "2") (pinfunction "2_2") (pintype "passive"))
      (node (ref "C11") (pin "2") (pinfunction "2_2") (pintype "passive"))
      (node (ref "C12") (pin "-") (pinfunction "2_-") (pintype "passive"))
      (node (ref "C13") (pin "2") (pinfunction "2_2") (pintype "passive"))
      (node (ref "C14") (pin "2") (pinfunction "2_2") (pintype "passive"))
      (node (ref "C15") (pin "2") (pinfunction "2_2") (pintype "passive"))
      (node (ref "C16") (pin "2") (pinfunction "2_2") (pintype "passive"))
      (node (ref "C17") (pin "2") (pinfunction "2_2") (pintype "passive"))
      (node (ref "C18") (pin "2") (pinfunction "2_2") (pintype "passive"))
      (node (ref "C19") (pin "2") (pinfunction "2_2") (pintype "passive"))
      (node (ref "C2") (pin "2") (pinfunction "2_2") (pintype "passive"))
      (node (ref "C20") (pin "2") (pinfunction "2_2") (pintype "passive"))
      (node (ref "C21") (pin "2") (pinfunction "2_2") (pintype "passive"))
      (node (ref "C22") (pin "2") (pinfunction "2_2") (pintype "passive"))
      (node (ref "C23") (pin "2") (pinfunction "2_2") (pintype "passive"))
      (node (ref "C24") (pin "-") (pinfunction "2_-") (pintype "passive"))
      (node (ref "C25") (pin "2") (pinfunction "2_2") (pintype "passive"))
      (node (ref "C26") (pin "2") (pinfunction "2_2") (pintype "passive"))
      (node (ref "C27") (pin "2") (pinfunction "2_2") (pintype "passive"))
      (node (ref "C28") (pin "2") (pinfunction "2_2") (pintype "passive"))
      (node (ref "C3") (pin "2") (pinfunction "2_2") (pintype "passive"))
      (node (ref "C4") (pin "2") (pinfunction "2_2") (pintype "passive"))
      (node (ref "C5") (pin "2") (pinfunction "2_2") (pintype "passive"))
      (node (ref "C6") (pin "2") (pinfunction "2_2") (pintype "passive"))
      (node (ref "C7") (pin "2") (pinfunction "2_2") (pintype "passive"))
      (node (ref "C8") (pin "2") (pinfunction "2_2") (pintype "passive"))
      (node (ref "C9") (pin "2") (pinfunction "2_2") (pintype "passive"))
      (node (ref "CON1") (pin "GND") (pinfunction "GND_GND") (pintype "bidirectional"))
      (node (ref "CON2") (pin "6") (pinfunction "VSS_6") (pintype "power_in"))
      (node (ref "CON2") (pin "G1") (pinfunction "GND1_G1") (pintype "power_in"))
      (node (ref "CON2") (pin "G2") (pinfunction "GND2_G2") (pintype "power_in"))
      (node (ref "CON2") (pin "G3") (pinfunction "GND3_G3") (pintype "power_in"))
      (node (ref "CON2") (pin "G4") (pinfunction "GND4_G4") (pintype "power_in"))
      (node (ref "D1") (pin "2") (pinfunction "GND_2") (pintype "power_in"))
      (node (ref "J1") (pin "4") (pinfunction "4_4") (pintype "passive"))
      (node (ref "J1") (pin "7") (pinfunction "7_7") (pintype "passive"))
      (node (ref "J2") (pin "4") (pinfunction "4_4") (pintype "passive"))
      (node (ref "J3") (pin "1") (pinfunction "1_1") (pintype "passive"))
      (node (ref "J4") (pin "2") (pinfunction "2_2") (pintype "passive"))
      (node (ref "J5") (pin "1") (pinfunction "1_1") (pintype "passive"))
      (node (ref "J6") (pin "1") (pinfunction "1_1") (pintype "passive"))
      (node (ref "PB1") (pin "SHIELD1") (pinfunction "CASE_SHIELD1") (pintype "passive"))
      (node (ref "PB2") (pin "1") (pinfunction "1_1") (pintype "passive"))
      (node (ref "PB2") (pin "2") (pinfunction "2_2") (pintype "passive"))
      (node (ref "Q5") (pin "2") (pinfunction "S_2") (pintype "passive"))
      (node (ref "R12") (pin "2") (pinfunction "2_2") (pintype "passive"))
      (node (ref "R13") (pin "2") (pinfunction "2_2") (pintype "passive"))
      (node (ref "R15") (pin "2") (pinfunction "2_2") (pintype "passive"))
      (node (ref "R16") (pin "2") (pinfunction "2_2") (pintype "passive"))
      (node (ref "R18") (pin "2") (pinfunction "2_2") (pintype "passive"))
      (node (ref "R2") (pin "1") (pinfunction "1_1") (pintype "passive"))
      (node (ref "R21") (pin "2") (pinfunction "2_2") (pintype "passive"))
      (node (ref "R23") (pin "2") (pinfunction "2_2") (pintype "passive"))
      (node (ref "R25") (pin "1") (pinfunction "1_1") (pintype "passive"))
      (node (ref "R39") (pin "1") (pinfunction "1_1") (pintype "passive"))
      (node (ref "R4") (pin "2") (pinfunction "2_2") (pintype "passive"))
      (node (ref "R6") (pin "2") (pinfunction "2_2") (pintype "passive"))
      (node (ref "R7") (pin "2") (pinfunction "2_2") (pintype "passive"))
      (node (ref "R8") (pin "2") (pinfunction "2_2") (pintype "passive"))
      (node (ref "U1") (pin "18") (pinfunction "GND2_18") (pintype "power_in"))
      (node (ref "U1") (pin "21") (pinfunction "GND3_21") (pintype "power_in"))
      (node (ref "U1") (pin "25") (pinfunction "AGND_25") (pintype "power_in"))
      (node (ref "U1") (pin "26") (pinfunction "TEST_26") (pintype "input"))
      (node (ref "U1") (pin "7") (pinfunction "GND1_7") (pintype "power_in"))
      (node (ref "U2") (pin "10") (pinfunction "GND1_10") (pintype "power_in"))
      (node (ref "U2") (pin "11") (pinfunction "GND2_11") (pintype "power_in"))
      (node (ref "U2") (pin "3") (pinfunction "SEL_3") (pintype "input"))
      (node (ref "U3") (pin "10") (pinfunction "ILIM0_10") (pintype "bidirectional"))
      (node (ref "U3") (pin "2") (pinfunction "GND1_2") (pintype "power_in"))
      (node (ref "U3") (pin "9") (pinfunction "GND2_9") (pintype "power_in"))
      (node (ref "U4") (pin "5") (pinfunction "GND_5") (pintype "power_in"))
      (node (ref "U5") (pin "4") (pinfunction "GND_4") (pintype "power_in"))
      (node (ref "U5") (pin "7") (pinfunction "A0_7") (pintype "input"))
      (node (ref "U5") (pin "8") (pinfunction "A1_8") (pintype "input"))
      (node (ref "U6") (pin "2") (pinfunction "A_2") (pintype "passive"))
    )
    (net (code "7") (name "HSPI_MISO") (class "Default")
      (node (ref "A1") (pin "5") (pinfunction "IO39/SENSOR_VN_5") (pintype "input"))
      (node (ref "J1") (pin "6") (pinfunction "6_6") (pintype "passive"))
    )
    (net (code "8") (name "HSPI_SCK") (class "Default")
      (node (ref "J1") (pin "5") (pinfunction "5_5") (pintype "passive"))
      (node (ref "R36") (pin "2") (pinfunction "2_2") (pintype "passive"))
    )
    (net (code "9") (name "H_SCK") (class "Default")
      (node (ref "A1") (pin "31") (pinfunction "IO19_31") (pintype "bidirectional"))
      (node (ref "R36") (pin "1") (pinfunction "1_1") (pintype "passive"))
    )
    (net (code "10") (name "IO0") (class "Default")
      (node (ref "A1") (pin "25") (pinfunction "IO0_25") (pintype "bidirectional"))
      (node (ref "Q3") (pin "C") (pinfunction "C_C") (pintype "passive"))
    )
    (net (code "11") (name "IO2_MMC_D0") (class "Default")
      (node (ref "A1") (pin "24") (pinfunction "IO2_24") (pintype "bidirectional"))
      (node (ref "CON2") (pin "7") (pinfunction "DAT0_DO_7") (pintype "bidirectional"))
      (node (ref "Q4") (pin "C") (pinfunction "C_C") (pintype "passive"))
      (node (ref "R34") (pin "1") (pinfunction "1_1") (pintype "passive"))
    )
    (net (code "12") (name "LCD_CSN") (class "Default")
      (node (ref "A1") (pin "30") (pinfunction "IO18_30") (pintype "bidirectional"))
      (node (ref "J4") (pin "3") (pinfunction "3_3") (pintype "passive"))
    )
    (net (code "13") (name "LCD_DC") (class "Default")
      (node (ref "A1") (pin "8") (pinfunction "IO32_8") (pintype "bidirectional"))
      (node (ref "J4") (pin "5") (pinfunction "5_5") (pintype "passive"))
    )
    (net (code "14") (name "LEP_CSN") (class "Default")
      (node (ref "A1") (pin "33") (pinfunction "IO21_33") (pintype "bidirectional"))
      (node (ref "J1") (pin "8") (pinfunction "8_8") (pintype "passive"))
    )
    (net (code "15") (name "MMC_CLK") (class "Default")
      (node (ref "A1") (pin "13") (pinfunction "IO14_13") (pintype "bidirectional"))
      (node (ref "CON2") (pin "5") (pinfunction "CLK_5") (pintype "input"))
      (node (ref "R33") (pin "1") (pinfunction "1_1") (pintype "passive"))
    )
    (net (code "16") (name "MMC_CMD") (class "Default")
      (node (ref "A1") (pin "23") (pinfunction "IO15_23") (pintype "bidirectional"))
      (node (ref "CON2") (pin "3") (pinfunction "CMD_DI_3") (pintype "input"))
      (node (ref "R32") (pin "1") (pinfunction "1_1") (pintype "passive"))
    )
    (net (code "17") (name "MMC_D1") (class "Default")
      (node (ref "A1") (pin "26") (pinfunction "IO4_26") (pintype "bidirectional"))
      (node (ref "CON2") (pin "8") (pinfunction "DAT1_8") (pintype "bidirectional"))
      (node (ref "R35") (pin "1") (pinfunction "1_1") (pintype "passive"))
    )
    (net (code "18") (name "MMC_D2") (class "Default")
      (node (ref "A1") (pin "14") (pinfunction "IO12_14") (pintype "bidirectional"))
      (node (ref "CON2") (pin "1") (pinfunction "DAT2_1") (pintype "bidirectional"))
    )
    (net (code "19") (name "MMC_D3") (class "Default")
      (node (ref "A1") (pin "16") (pinfunction "IO13_16") (pintype "bidirectional"))
      (node (ref "CON2") (pin "2") (pinfunction "DAT3_CS_2") (pintype "bidirectional"))
      (node (ref "R31") (pin "1") (pinfunction "1_1") (pintype "passive"))
    )
    (net (code "20") (name "Net-(D1-IO1$1)") (class "Default")
      (node (ref "D1") (pin "6") (pinfunction "IO1$1_6") (pintype "bidirectional"))
      (node (ref "U1") (pin "16") (pinfunction "USBDM_16") (pintype "bidirectional"))
    )
    (net (code "21") (name "Net-(D1-IO1)") (class "Default")
      (node (ref "CON1") (pin "D-") (pinfunction "D-_D-") (pintype "bidirectional"))
      (node (ref "D1") (pin "1") (pinfunction "IO1_1") (pintype "bidirectional"))
    )
    (net (code "22") (name "Net-(D1-IO2$1)") (class "Default")
      (node (ref "D1") (pin "4") (pinfunction "IO2$1_4") (pintype "bidirectional"))
      (node (ref "U1") (pin "15") (pinfunction "USBDP_15") (pintype "bidirectional"))
    )
    (net (code "23") (name "Net-(D1-IO2)") (class "Default")
      (node (ref "CON1") (pin "D+") (pinfunction "D+_D+") (pintype "bidirectional"))
      (node (ref "D1") (pin "3") (pinfunction "IO2_3") (pintype "bidirectional"))
    )
    (net (code "24") (name "Net-(D1-VBUS)") (class "Default")
      (node (ref "C1") (pin "1") (pinfunction "1_1") (pintype "passive"))
      (node (ref "CON1") (pin "VBUS") (pinfunction "VBUS_VBUS") (pintype "bidirectional"))
      (node (ref "D1") (pin "5") (pinfunction "VBUS_5") (pintype "power_in"))
      (node (ref "L1") (pin "1") (pinfunction "P$1_1") (pintype "passive"))
    )
    (net (code "25") (name "Net-(D4-A)") (class "Default")
      (node (ref "D4") (pin "P$1") (pinfunction "A_P$1") (pintype "passive"))
      (node (ref "R19") (pin "1") (pinfunction "1_1") (pintype "passive"))
    )
    (net (code "26") (name "Net-(L2-P$1)") (class "Default")
      (node (ref "L2") (pin "1") (pinfunction "P$1_1") (pintype "passive"))
      (node (ref "U3") (pin "1") (pinfunction "L1_1") (pintype "passive"))
    )
    (net (code "27") (name "Net-(L2-P$2)") (class "Default")
      (node (ref "L2") (pin "2") (pinfunction "P$2_2") (pintype "passive"))
      (node (ref "U3") (pin "3") (pinfunction "L2_3") (pintype "passive"))
    )
    (net (code "28") (name "Net-(PB2-Pad3)") (class "Default")
      (node (ref "PB2") (pin "3") (pinfunction "3_3") (pintype "passive"))
      (node (ref "Q2") (pin "C") (pinfunction "C_C") (pintype "passive"))
    )
    (net (code "29") (name "Net-(Q1-D)") (class "Default")
      (node (ref "Q1") (pin "3") (pinfunction "D_3") (pintype "passive"))
      (node (ref "R14") (pin "2") (pinfunction "2_2") (pintype "passive"))
    )
    (net (code "30") (name "Net-(Q2-PadB)") (class "Default")
      (node (ref "Q2") (pin "B") (pinfunction "B_B") (pintype "passive"))
      (node (ref "R27") (pin "2") (pinfunction "2_2") (pintype "passive"))
    )
    (net (code "31") (name "Net-(Q3-PadB)") (class "Default")
      (node (ref "Q3") (pin "B") (pinfunction "B_B") (pintype "passive"))
      (node (ref "R28") (pin "2") (pinfunction "2_2") (pintype "passive"))
    )
    (net (code "32") (name "Net-(Q4-PadB)") (class "Default")
      (node (ref "Q4") (pin "B") (pinfunction "B_B") (pintype "passive"))
      (node (ref "R29") (pin "2") (pinfunction "2_2") (pintype "passive"))
    )
    (net (code "33") (name "Net-(Q5-D)") (class "Default")
      (node (ref "Q5") (pin "3") (pinfunction "D_3") (pintype "passive"))
      (node (ref "Q6") (pin "1") (pinfunction "G_1") (pintype "passive"))
      (node (ref "R38") (pin "1") (pinfunction "1_1") (pintype "passive"))
    )
    (net (code "34") (name "Net-(Q6-D)") (class "Default")
      (node (ref "J4") (pin "1") (pinfunction "1_1") (pintype "passive"))
      (node (ref "Q6") (pin "3") (pinfunction "D_3") (pintype "passive"))
      (node (ref "R39") (pin "2") (pinfunction "2_2") (pintype "passive"))
    )
    (net (code "35") (name "Net-(R11-Pad2)") (class "Default")
      (node (ref "R11") (pin "2") (pinfunction "2_2") (pintype "passive"))
      (node (ref "R12") (pin "1") (pinfunction "1_1") (pintype "passive"))
      (node (ref "R13") (pin "1") (pinfunction "1_1") (pintype "passive"))
    )
    (net (code "36") (name "Net-(U1-3V3OUT)") (class "Default")
      (node (ref "C3") (pin "1") (pinfunction "1_1") (pintype "passive"))
      (node (ref "U1") (pin "17") (pinfunction "3V3OUT_17") (pintype "output"))
      (node (ref "U1") (pin "4") (pinfunction "VCCIO_4") (pintype "power_in"))
    )
    (net (code "37") (name "Net-(U1-CBUS2)") (class "Default")
      (node (ref "R24") (pin "2") (pinfunction "2_2") (pintype "passive"))
      (node (ref "U1") (pin "13") (pinfunction "CBUS2_13") (pintype "bidirectional"))
    )
    (net (code "38") (name "Net-(U1-TXD)") (class "Default")
      (node (ref "D2") (pin "C") (pinfunction "C_C") (pintype "passive"))
      (node (ref "U1") (pin "1") (pinfunction "TXD_1") (pintype "output"))
    )
    (net (code "39") (name "Net-(U1-_RESET)") (class "Default")
      (node (ref "R1") (pin "1") (pinfunction "1_1") (pintype "passive"))
      (node (ref "R2") (pin "2") (pinfunction "2_2") (pintype "passive"))
      (node (ref "U1") (pin "19") (pinfunction "_RESET_19") (pintype "input"))
    )
    (net (code "40") (name "Net-(U2-CE)") (class "Default")
      (node (ref "R10") (pin "2") (pinfunction "2_2") (pintype "passive"))
      (node (ref "U2") (pin "17") (pinfunction "CE_17") (pintype "input"))
    )
    (net (code "41") (name "Net-(U2-PROG1)") (class "Default")
      (node (ref "R6") (pin "1") (pinfunction "1_1") (pintype "passive"))
      (node (ref "U2") (pin "13") (pinfunction "PROG1_13") (pintype "input"))
    )
    (net (code "42") (name "Net-(U2-PROG3)") (class "Default")
      (node (ref "R7") (pin "1") (pinfunction "1_1") (pintype "passive"))
      (node (ref "R8") (pin "1") (pinfunction "1_1") (pintype "passive"))
      (node (ref "U2") (pin "12") (pinfunction "PROG3_12") (pintype "input"))
    )
    (net (code "43") (name "Net-(U2-THERM)") (class "Default")
      (node (ref "R11") (pin "1") (pinfunction "1_1") (pintype "passive"))
      (node (ref "U2") (pin "5") (pinfunction "THERM_5") (pintype "input"))
    )
    (net (code "44") (name "Net-(U2-VPCC)") (class "Default")
      (node (ref "R4") (pin "1") (pinfunction "1_1") (pintype "passive"))
      (node (ref "R5") (pin "2") (pinfunction "2_2") (pintype "passive"))
      (node (ref "U2") (pin "2") (pinfunction "VPCC_2") (pintype "input"))
    )
    (net (code "45") (name "Net-(U2-{slash}TE)") (class "Default")
      (node (ref "R9") (pin "2") (pinfunction "2_2") (pintype "passive"))
      (node (ref "U2") (pin "9") (pinfunction "/TE_9") (pintype "input"))
    )
    (net (code "46") (name "Net-(U3-SS)") (class "Default")
      (node (ref "C10") (pin "1") (pinfunction "1_1") (pintype "passive"))
      (node (ref "U3") (pin "7") (pinfunction "SS_7") (pintype "passive"))
    )
    (net (code "47") (name "Net-(U4-VBATT)") (class "Default")
      (node (ref "BAT2") (pin "+2") (pinfunction "+2_+2") (pintype "power_in"))
      (node (ref "U4") (pin "6") (pinfunction "VBATT_6") (pintype "power_in"))
    )
    (net (code "48") (name "Net-(U5-REF)") (class "Default")
      (node (ref "C18") (pin "1") (pinfunction "1_1") (pintype "passive"))
      (node (ref "C19") (pin "1") (pinfunction "1_1") (pintype "passive"))
      (node (ref "R30") (pin "1") (pinfunction "1_1") (pintype "passive"))
      (node (ref "U5") (pin "1") (pinfunction "REF_1") (pintype "input"))
      (node (ref "U6") (pin "1") (pinfunction "C_1") (pintype "passive"))
    )
    (net (code "49") (name "PWR_EN") (class "Default")
      (node (ref "D3") (pin "C") (pinfunction "C_C") (pintype "passive"))
      (node (ref "PB1") (pin "2") (pinfunction "2_2") (pintype "passive"))
      (node (ref "Q5") (pin "1") (pinfunction "G_1") (pintype "passive"))
      (node (ref "R17") (pin "1") (pinfunction "1_1") (pintype "passive"))
      (node (ref "U3") (pin "11") (pinfunction "EN_11") (pintype "bidirectional"))
    )
    (net (code "50") (name "PWR_HOLD") (class "Default")
      (node (ref "A1") (pin "11") (pinfunction "IO26_11") (pintype "bidirectional"))
      (node (ref "D3") (pin "A") (pinfunction "A_A") (pintype "passive"))
      (node (ref "J4") (pin "8") (pinfunction "8_8") (pintype "passive"))
      (node (ref "Q1") (pin "1") (pinfunction "G_1") (pintype "passive"))
      (node (ref "R16") (pin "1") (pinfunction "1_1") (pintype "passive"))
    )
    (net (code "51") (name "RST_N") (class "Default")
      (node (ref "A1") (pin "3") (pinfunction "EN_3") (pintype "input"))
      (node (ref "C15") (pin "1") (pinfunction "1_1") (pintype "passive"))
      (node (ref "J4") (pin "4") (pinfunction "4_4") (pintype "passive"))
      (node (ref "PB2") (pin "4") (pinfunction "4_4") (pintype "passive"))
      (node (ref "R26") (pin "1") (pinfunction "1_1") (pintype "passive"))
    )
    (net (code "52") (name "RTS_N") (class "Default")
      (node (ref "Q2") (pin "E") (pinfunction "E_E") (pintype "passive"))
      (node (ref "R28") (pin "1") (pinfunction "1_1") (pintype "passive"))
      (node (ref "R29") (pin "1") (pinfunction "1_1") (pintype "passive"))
      (node (ref "U1") (pin "3") (pinfunction "_RTS_3") (pintype "output"))
    )
    (net (code "53") (name "RXD") (class "Default")
      (node (ref "A1") (pin "35") (pinfunction "IO1/TXD0_35") (pintype "bidirectional"))
      (node (ref "U1") (pin "5") (pinfunction "RXD_5") (pintype "input"))
    )
    (net (code "54") (name "SCL") (class "Default")
      (node (ref "A1") (pin "37") (pinfunction "IO23_37") (pintype "bidirectional"))
      (node (ref "J1") (pin "1") (pinfunction "1_1") (pintype "passive"))
      (node (ref "J2") (pin "1") (pinfunction "1_1") (pintype "passive"))
      (node (ref "J5") (pin "4") (pinfunction "4_4") (pintype "passive"))
      (node (ref "U4") (pin "8") (pinfunction "SCL_8") (pintype "input"))
      (node (ref "U5") (pin "3") (pinfunction "SCL_3") (pintype "input"))
    )
    (net (code "55") (name "SDA") (class "Default")
      (node (ref "A1") (pin "36") (pinfunction "IO22_36") (pintype "bidirectional"))
      (node (ref "J1") (pin "2") (pinfunction "2_2") (pintype "passive"))
      (node (ref "J2") (pin "2") (pinfunction "2_2") (pintype "passive"))
      (node (ref "J5") (pin "3") (pinfunction "3_3") (pintype "passive"))
      (node (ref "U4") (pin "7") (pinfunction "SDA_7") (pintype "bidirectional"))
      (node (ref "U5") (pin "2") (pinfunction "SDA_2") (pintype "bidirectional"))
    )
    (net (code "56") (name "SLEEP_N") (class "Default")
      (node (ref "R10") (pin "1") (pinfunction "1_1") (pintype "passive"))
      (node (ref "U1") (pin "12") (pinfunction "CBUS4_12") (pintype "bidirectional"))
    )
    (net (code "57") (name "SNS_AUX1") (class "Default")
      (node (ref "J6") (pin "3") (pinfunction "3_3") (pintype "passive"))
      (node (ref "U5") (pin "9") (pinfunction "CH7_9") (pintype "input"))
    )
    (net (code "58") (name "SNS_AUX2") (class "Default")
      (node (ref "J6") (pin "2") (pinfunction "2_2") (pintype "passive"))
      (node (ref "U5") (pin "10") (pinfunction "CH6_10") (pintype "input"))
    )
    (net (code "59") (name "SNS_BATT") (class "Default")
      (node (ref "Q1") (pin "2") (pinfunction "S_2") (pintype "passive"))
      (node (ref "R15") (pin "1") (pinfunction "1_1") (pintype "passive"))
      (node (ref "U5") (pin "14") (pinfunction "CH2_14") (pintype "input"))
    )
    (net (code "60") (name "SNS_BTN") (class "Default")
      (node (ref "R17") (pin "2") (pinfunction "2_2") (pintype "passive"))
      (node (ref "R18") (pin "1") (pinfunction "1_1") (pintype "passive"))
      (node (ref "U5") (pin "16") (pinfunction "CH0_16") (pintype "input"))
    )
    (net (code "61") (name "SNS_PWREN") (class "Default")
      (node (ref "R24") (pin "1") (pinfunction "1_1") (pintype "passive"))
      (node (ref "R25") (pin "2") (pinfunction "2_2") (pintype "passive"))
      (node (ref "U5") (pin "13") (pinfunction "CH3_13") (pintype "input"))
    )
    (net (code "62") (name "SNS_STAT1") (class "Default")
      (node (ref "D5") (pin "A") (pinfunction "A_A") (pintype "passive"))
      (node (ref "R20") (pin "2") (pinfunction "2_2") (pintype "passive"))
      (node (ref "R21") (pin "1") (pinfunction "1_1") (pintype "passive"))
      (node (ref "U5") (pin "12") (pinfunction "CH4_12") (pintype "input"))
    )
    (net (code "63") (name "SNS_STAT2") (class "Default")
      (node (ref "R22") (pin "2") (pinfunction "2_2") (pintype "passive"))
      (node (ref "R23") (pin "1") (pinfunction "1_1") (pintype "passive"))
      (node (ref "U2") (pin "7") (pinfunction "STAT2_7") (pintype "output"))
      (node (ref "U5") (pin "15") (pinfunction "CH1_15") (pintype "input"))
    )
    (net (code "64") (name "SNS_T") (class "Default")
      (node (ref "C26") (pin "1") (pinfunction "1_1") (pintype "passive"))
      (node (ref "J3") (pin "2") (pinfunction "2_2") (pintype "passive"))
      (node (ref "U5") (pin "11") (pinfunction "CH5_11") (pintype "input"))
    )
    (net (code "65") (name "STAT1") (class "Default")
      (node (ref "D4") (pin "P$2") (pinfunction "C_P$2") (pintype "passive"))
      (node (ref "D5") (pin "C") (pinfunction "C_C") (pintype "passive"))
      (node (ref "U2") (pin "8") (pinfunction "STAT1/LBO_8") (pintype "output"))
    )
    (net (code "66") (name "TS_CSN") (class "Default")
      (node (ref "A1") (pin "29") (pinfunction "IO5_29") (pintype "bidirectional"))
      (node (ref "J4") (pin "10") (pinfunction "10_10") (pintype "passive"))
    )
    (net (code "67") (name "TS_IRQ") (class "Default")
      (node (ref "A1") (pin "7") (pinfunction "IO35_7") (pintype "input"))
      (node (ref "J4") (pin "11") (pinfunction "11_11") (pintype "passive"))
    )
    (net (code "68") (name "TXD") (class "Default")
      (node (ref "A1") (pin "34") (pinfunction "IO3/RXD0_34") (pintype "bidirectional"))
      (node (ref "D2") (pin "A") (pinfunction "A_A") (pintype "passive"))
      (node (ref "R3") (pin "1") (pinfunction "1_1") (pintype "passive"))
    )
    (net (code "69") (name "V+") (class "Default")
      (node (ref "C8") (pin "1") (pinfunction "1_1") (pintype "passive"))
      (node (ref "C9") (pin "1") (pinfunction "1_1") (pintype "passive"))
      (node (ref "PB1") (pin "1") (pinfunction "1_1") (pintype "passive"))
      (node (ref "Q6") (pin "2") (pinfunction "S_2") (pintype "passive"))
      (node (ref "R38") (pin "2") (pinfunction "2_2") (pintype "passive"))
      (node (ref "U2") (pin "1") (pinfunction "OUT1_1") (pintype "output"))
      (node (ref "U2") (pin "20") (pinfunction "OUT2_20") (pintype "output"))
      (node (ref "U3") (pin "12") (pinfunction "VIN_12") (pintype "power_in"))
      (node (ref "U3") (pin "6") (pinfunction "PFM/PWM_6") (pintype "bidirectional"))
    )
    (net (code "70") (name "VBATT") (class "Default")
      (node (ref "BAT1") (pin "+") (pinfunction "+_+") (pintype "power_in"))
      (node (ref "C7") (pin "1") (pinfunction "1_1") (pintype "passive"))
      (node (ref "R14") (pin "1") (pinfunction "1_1") (pintype "passive"))
      (node (ref "U2") (pin "14") (pinfunction "VBAT1_14") (pintype "output"))
      (node (ref "U2") (pin "15") (pinfunction "VBAT2_15") (pintype "output"))
      (node (ref "U2") (pin "16") (pinfunction "VBAT3_16") (pintype "output"))
    )
    (net (code "71") (name "VSPI_MISO") (class "Default")
      (node (ref "A1") (pin "6") (pinfunction "IO34_6") (pintype "input"))
      (node (ref "J2") (pin "6") (pinfunction "6_6") (pintype "passive"))
      (node (ref "J4") (pin "9") (pinfunction "9_9") (pintype "passive"))
    )
    (net (code "72") (name "VSPI_MOSI") (class "Default")
      (node (ref "A1") (pin "9") (pinfunction "IO33_9") (pintype "bidirectional"))
      (node (ref "J2") (pin "7") (pinfunction "7_7") (pintype "passive"))
      (node (ref "J4") (pin "6") (pinfunction "6_6") (pintype "passive"))
    )
    (net (code "73") (name "VSPI_SCK") (class "Default")
      (node (ref "J2") (pin "5") (pinfunction "5_5") (pintype "passive"))
      (node (ref "J4") (pin "7") (pinfunction "7_7") (pintype "passive"))
      (node (ref "R37") (pin "2") (pinfunction "2_2") (pintype "passive"))
    )
    (net (code "74") (name "VSYNC") (class "Default")
      (node (ref "A1") (pin "4") (pinfunction "IO36/SENSOR_VP_4") (pintype "input"))
      (node (ref "J1") (pin "9") (pinfunction "9_9") (pintype "passive"))
    )
    (net (code "75") (name "V_SCK") (class "Default")
      (node (ref "A1") (pin "10") (pinfunction "IO25_10") (pintype "bidirectional"))
      (node (ref "R37") (pin "1") (pinfunction "1_1") (pintype "passive"))
    )
    (net (code "76") (name "unconnected-(A1-IO6{slash}SCK-Pad20)") (class "Default")
      (node (ref "A1") (pin "20") (pinfunction "IO6/SCK_20") (pintype "bidirectional"))
    )
    (net (code "77") (name "unconnected-(A1-IO7{slash}SDO-Pad21)") (class "Default")
      (node (ref "A1") (pin "21") (pinfunction "IO7/SDO_21") (pintype "bidirectional"))
    )
    (net (code "78") (name "unconnected-(A1-IO8{slash}SDI-Pad22)") (class "Default")
      (node (ref "A1") (pin "22") (pinfunction "IO8/SDI_22") (pintype "bidirectional"))
    )
    (net (code "79") (name "unconnected-(A1-IO9{slash}SHD-Pad17)") (class "Default")
      (node (ref "A1") (pin "17") (pinfunction "IO9/SHD_17") (pintype "bidirectional"))
    )
    (net (code "80") (name "unconnected-(A1-IO10{slash}SWP-Pad18)") (class "Default")
      (node (ref "A1") (pin "18") (pinfunction "IO10/SWP_18") (pintype "bidirectional"))
    )
    (net (code "81") (name "unconnected-(A1-IO11{slash}SCS-Pad19)") (class "Default")
      (node (ref "A1") (pin "19") (pinfunction "IO11/SCS_19") (pintype "bidirectional"))
    )
    (net (code "82") (name "unconnected-(CON2-PadSW1)") (class "Default")
      (node (ref "CON2") (pin "SW1") (pinfunction "SW1_SW1") (pintype "passive"))
    )
    (net (code "83") (name "unconnected-(CON2-PadSW2)") (class "Default")
      (node (ref "CON2") (pin "SW2") (pinfunction "SW2_SW2") (pintype "passive"))
    )
    (net (code "84") (name "unconnected-(J1-Pad10)") (class "Default")
      (node (ref "J1") (pin "10") (pinfunction "10_10") (pintype "passive"))
    )
    (net (code "85") (name "unconnected-(U1-CBUS0-Pad23)") (class "Default")
      (node (ref "U1") (pin "23") (pinfunction "CBUS0_23") (pintype "bidirectional"))
    )
    (net (code "86") (name "unconnected-(U1-CBUS1-Pad22)") (class "Default")
      (node (ref "U1") (pin "22") (pinfunction "CBUS1_22") (pintype "bidirectional"))
    )
    (net (code "87") (name "unconnected-(U1-CBUS3-Pad14)") (class "Default")
      (node (ref "U1") (pin "14") (pinfunction "CBUS3_14") (pintype "bidirectional"))
    )
    (net (code "88") (name "unconnected-(U1-OSCI-Pad27)") (class "Default")
      (node (ref "U1") (pin "27") (pinfunction "OSCI_27") (pintype "input"))
    )
    (net (code "89") (name "unconnected-(U1-OSCO-Pad28)") (class "Default")
      (node (ref "U1") (pin "28") (pinfunction "OSCO_28") (pintype "output"))
    )
    (net (code "90") (name "unconnected-(U1-_CTS-Pad11)") (class "Default")
      (node (ref "U1") (pin "11") (pinfunction "_CTS_11") (pintype "input"))
    )
    (net (code "91") (name "unconnected-(U1-_DCD-Pad10)") (class "Default")
      (node (ref "U1") (pin "10") (pinfunction "_DCD_10") (pintype "input"))
    )
    (net (code "92") (name "unconnected-(U1-_DSR-Pad9)") (class "Default")
      (node (ref "U1") (pin "9") (pinfunction "_DSR_9") (pintype "input"))
    )
    (net (code "93") (name "unconnected-(U1-_RI-Pad6)") (class "Default")
      (node (ref "U1") (pin "6") (pinfunction "_RI_6") (pintype "input"))
    )
    (net (code "94") (name "unconnected-(U2-{slash}PG-Pad6)") (class "Default")
      (node (ref "U2") (pin "6") (pinfunction "/PG_6") (pintype "output"))
    )
    (net (code "95") (name "unconnected-(U3-PG-Pad8)") (class "Default")
      (node (ref "U3") (pin "8") (pinfunction "PG_8") (pintype "bidirectional"))
    )
    (net (code "96") (name "unconnected-(U4-32KHZ-Pad1)") (class "Default")
      (node (ref "U4") (pin "1") (pinfunction "32KHZ_1") (pintype "output"))
    )
    (net (code "97") (name "unconnected-(U4-INT-Pad3)") (class "Default")
      (node (ref "U4") (pin "3") (pinfunction "INT_3") (pintype "output"))
    )
    (net (code "98") (name "unconnected-(U4-RST_N-Pad4)") (class "Default")
      (node (ref "U4") (pin "4") (pinfunction "RST_N_4") (pintype "bidirectional"))
    )
    (net (code "99") (name "unconnected-(U5-INT-Pad6)") (class "Default")
      (node (ref "U5") (pin "6") (pinfunction "INT_6") (pintype "output"))
    )
  )
)
